# DBPIC18DIPv1_7.net
KiCad netlist of a schematic drawn in EAGLE
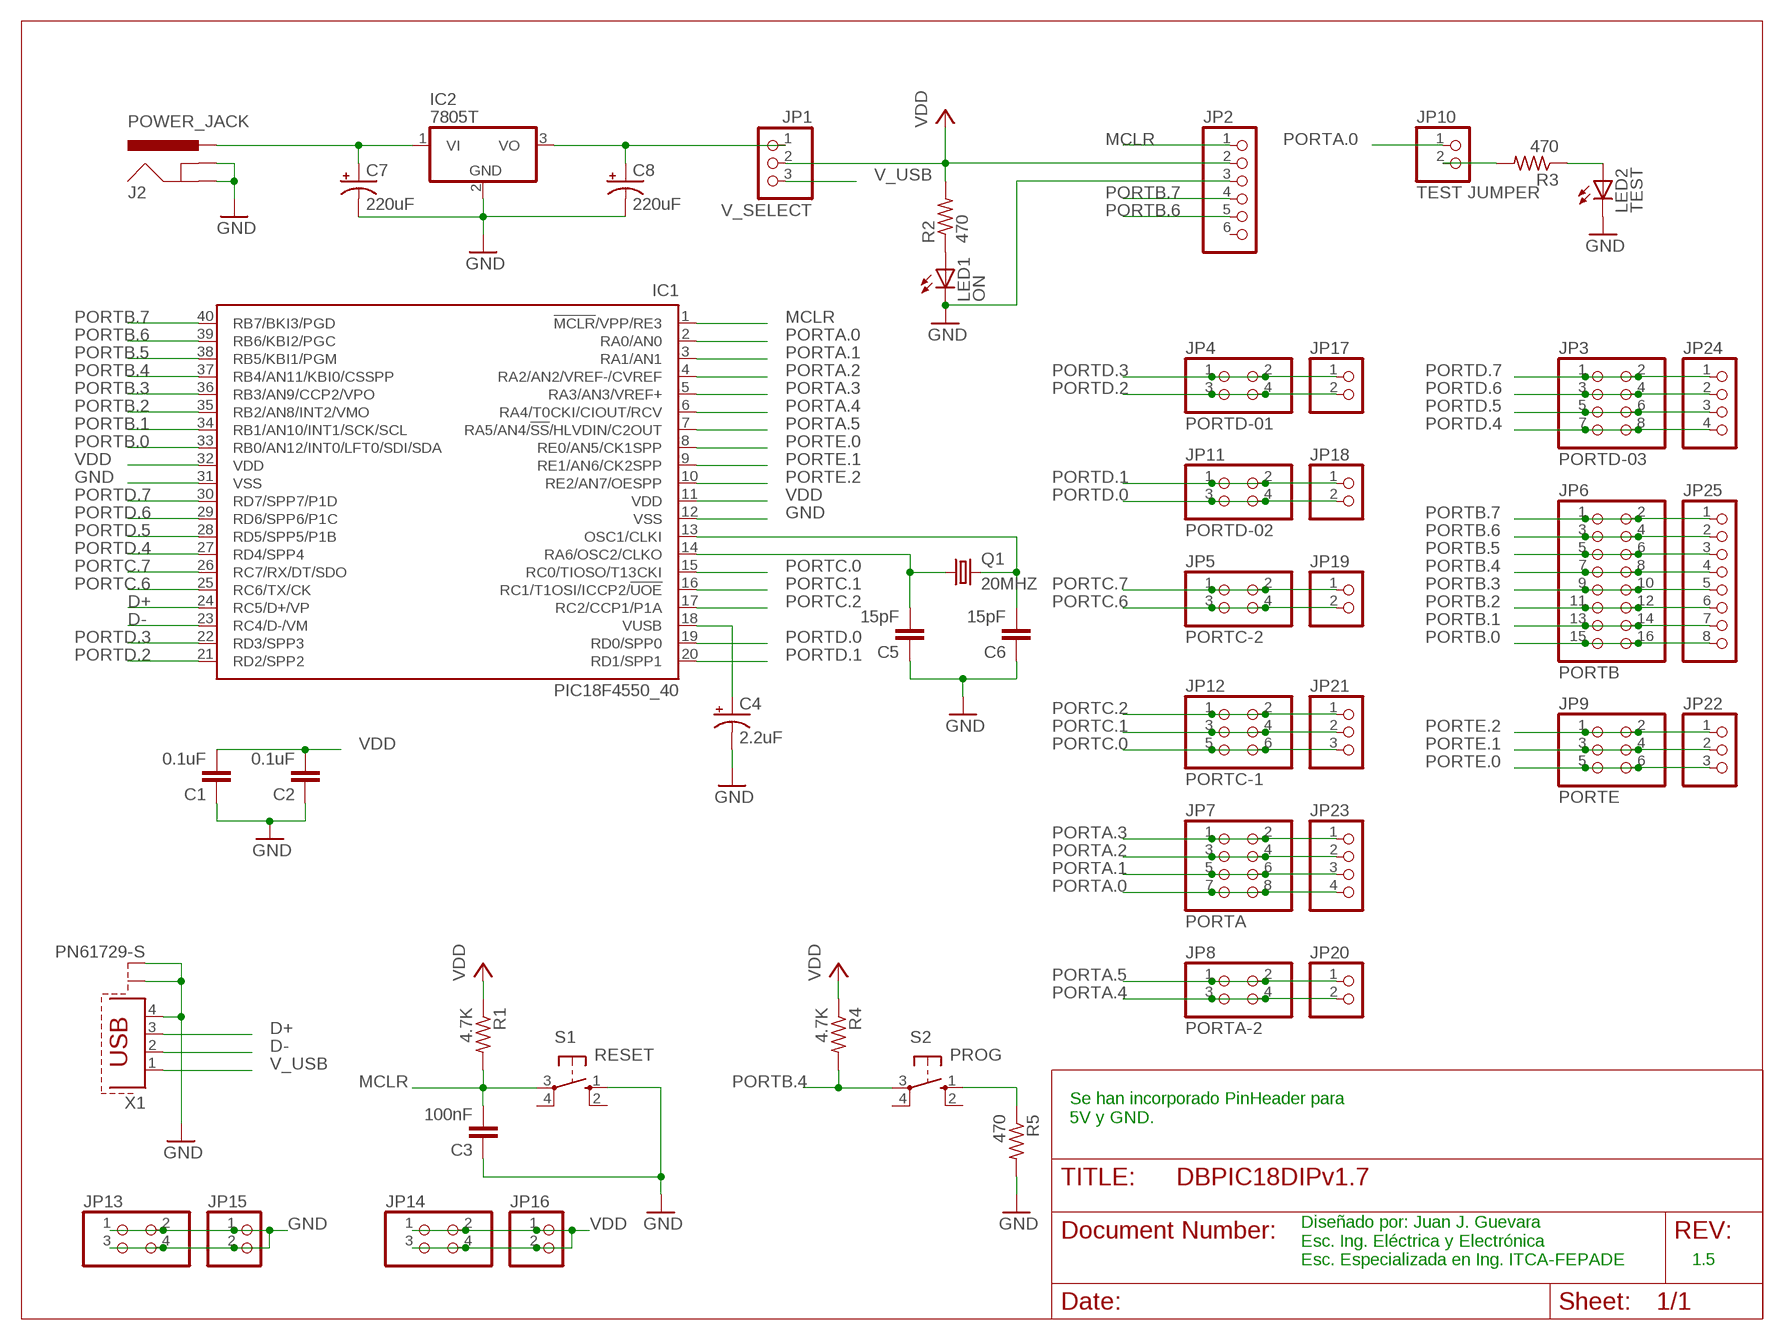
[diagram p0: schematic, sheet 1]

(export (version "E")
  (design (tool "Eeschema 10.0.6"))
  (components
    (comp (ref "C1")
      (value "0.1uF")
      (footprint "eagle-import:C2.5-2")
      (libsource (lib "eagle-import") (part "C2.5/2"))
    )
    (comp (ref "C2")
      (value "0.1uF")
      (footprint "eagle-import:C2.5-2")
      (libsource (lib "eagle-import") (part "C2.5/2"))
    )
    (comp (ref "C3")
      (value "100nF")
      (footprint "eagle-import:C2.5-2")
      (libsource (lib "eagle-import") (part "C2.5/2"))
    )
    (comp (ref "C4")
      (value "2.2uF")
      (footprint "eagle-import:E1,8-4")
      (libsource (lib "eagle-import") (part "CPOL-USE1.8-4"))
    )
    (comp (ref "C5")
      (value "15pF")
      (footprint "eagle-import:C2.5-2")
      (libsource (lib "eagle-import") (part "C2.5/2"))
    )
    (comp (ref "C6")
      (value "15pF")
      (footprint "eagle-import:C2.5-2")
      (libsource (lib "eagle-import") (part "C2.5/2"))
    )
    (comp (ref "C7")
      (value "220uF")
      (footprint "eagle-import:E2-5")
      (libsource (lib "eagle-import") (part "CPOL-USE2-5"))
    )
    (comp (ref "C8")
      (value "220uF")
      (footprint "eagle-import:E1,8-4")
      (libsource (lib "eagle-import") (part "CPOL-USE1.8-4"))
    )
    (comp (ref "IC1")
      (value "PIC18F4550_40")
      (footprint "eagle-import:DIL40")
      (fields (field (name "MF") "MICROCHIP") (field (name "MPN") "PIC18F4550-I/P"))
      (libsource (lib "eagle-import") (part "PIC18F4_40550"))
    )
    (comp (ref "IC2")
      (value "7805T")
      (footprint "eagle-import:TO220H")
      (libsource (lib "eagle-import") (part "78T05"))
    )
    (comp (ref "J2")
      (value "POWER_JACK")
      (footprint "eagle-import:POWER_JACK_PTH")
      (libsource (lib "eagle-import") (part "POWER_JACK"))
    )
    (comp (ref "JP1")
      (value "V_SELECT")
      (footprint "eagle-import:1X03")
      (libsource (lib "eagle-import") (part "PINHD-1X3"))
    )
    (comp (ref "JP2")
      (value "PINHD-1X6")
      (footprint "eagle-import:1X06")
      (libsource (lib "eagle-import") (part "PINHD-1X6"))
    )
    (comp (ref "JP3")
      (value "PORTD-03")
      (footprint "eagle-import:2X04")
      (libsource (lib "eagle-import") (part "PINHD-2X4"))
    )
    (comp (ref "JP4")
      (value "PORTD-01")
      (footprint "eagle-import:2X02")
      (libsource (lib "eagle-import") (part "PINHD-2X2"))
    )
    (comp (ref "JP5")
      (value "PORTC-2")
      (footprint "eagle-import:2X02")
      (libsource (lib "eagle-import") (part "PINHD-2X2"))
    )
    (comp (ref "JP6")
      (value "PORTB")
      (footprint "eagle-import:2X08")
      (libsource (lib "eagle-import") (part "PINHD-2X8"))
    )
    (comp (ref "JP7")
      (value "PORTA")
      (footprint "eagle-import:2X04")
      (libsource (lib "eagle-import") (part "PINHD-2X4"))
    )
    (comp (ref "JP8")
      (value "PORTA-2")
      (footprint "eagle-import:2X02")
      (libsource (lib "eagle-import") (part "PINHD-2X2"))
    )
    (comp (ref "JP9")
      (value "PORTE")
      (footprint "eagle-import:2X03")
      (libsource (lib "eagle-import") (part "PINHD-2X3"))
    )
    (comp (ref "JP10")
      (value "TEST JUMPER")
      (footprint "eagle-import:1X02")
      (libsource (lib "eagle-import") (part "PINHD-1X2"))
    )
    (comp (ref "JP11")
      (value "PORTD-02")
      (footprint "eagle-import:2X02")
      (libsource (lib "eagle-import") (part "PINHD-2X2"))
    )
    (comp (ref "JP12")
      (value "PORTC-1")
      (footprint "eagle-import:2X03")
      (libsource (lib "eagle-import") (part "PINHD-2X3"))
    )
    (comp (ref "JP13")
      (value "PINHD-2X2")
      (footprint "eagle-import:2X02")
      (libsource (lib "eagle-import") (part "PINHD-2X2"))
    )
    (comp (ref "JP14")
      (value "PINHD-2X2")
      (footprint "eagle-import:2X02")
      (libsource (lib "eagle-import") (part "PINHD-2X2"))
    )
    (comp (ref "JP15")
      (value "PINHD-1X2")
      (footprint "eagle-import:1X02")
      (libsource (lib "eagle-import") (part "PINHD-1X2"))
    )
    (comp (ref "JP16")
      (value "PINHD-1X2")
      (footprint "eagle-import:1X02")
      (libsource (lib "eagle-import") (part "PINHD-1X2"))
    )
    (comp (ref "JP17")
      (value "PINHD-1X2")
      (footprint "eagle-import:1X02")
      (libsource (lib "eagle-import") (part "PINHD-1X2"))
    )
    (comp (ref "JP18")
      (value "PINHD-1X2")
      (footprint "eagle-import:1X02")
      (libsource (lib "eagle-import") (part "PINHD-1X2"))
    )
    (comp (ref "JP19")
      (value "PINHD-1X2")
      (footprint "eagle-import:1X02")
      (libsource (lib "eagle-import") (part "PINHD-1X2"))
    )
    (comp (ref "JP20")
      (value "PINHD-1X2")
      (footprint "eagle-import:1X02")
      (libsource (lib "eagle-import") (part "PINHD-1X2"))
    )
    (comp (ref "JP21")
      (value "PINHD-1X3")
      (footprint "eagle-import:1X03")
      (libsource (lib "eagle-import") (part "PINHD-1X3"))
    )
    (comp (ref "JP22")
      (value "PINHD-1X3")
      (footprint "eagle-import:1X03")
      (libsource (lib "eagle-import") (part "PINHD-1X3"))
    )
    (comp (ref "JP23")
      (value "PINHD-1X4")
      (footprint "eagle-import:1X04")
      (libsource (lib "eagle-import") (part "PINHD-1X4"))
    )
    (comp (ref "JP24")
      (value "PINHD-1X4")
      (footprint "eagle-import:1X04")
      (libsource (lib "eagle-import") (part "PINHD-1X4"))
    )
    (comp (ref "JP25")
      (value "PINHD-1X8")
      (footprint "eagle-import:1X08")
      (libsource (lib "eagle-import") (part "PINHD-1X8"))
    )
    (comp (ref "LED1")
      (value "ON")
      (footprint "eagle-import:LED3MM")
      (libsource (lib "eagle-import") (part "LED3MM"))
    )
    (comp (ref "LED2")
      (value "TEST")
      (footprint "eagle-import:LED3MM")
      (libsource (lib "eagle-import") (part "LED3MM"))
    )
    (comp (ref "Q1")
      (value "20MHZ")
      (footprint "eagle-import:HC49_S")
      (libsource (lib "eagle-import") (part "CRYSTALHC49S"))
    )
    (comp (ref "R1")
      (value "4.7K")
      (footprint "eagle-import:0207_12")
      (libsource (lib "eagle-import") (part "R-US_0207/12"))
    )
    (comp (ref "R2")
      (value "470")
      (footprint "eagle-import:0207_12")
      (libsource (lib "eagle-import") (part "R-US_0207/12"))
    )
    (comp (ref "R3")
      (value "470")
      (footprint "eagle-import:0207_12")
      (libsource (lib "eagle-import") (part "R-US_0207/12"))
    )
    (comp (ref "R4")
      (value "4.7K")
      (footprint "eagle-import:0207_12")
      (libsource (lib "eagle-import") (part "R-US_0207/12"))
    )
    (comp (ref "R5")
      (value "470")
      (footprint "eagle-import:0207_12")
      (libsource (lib "eagle-import") (part "R-US_0207/12"))
    )
    (comp (ref "S1")
      (value "RESET")
      (footprint "eagle-import:B3F-10XX")
      (fields (field (name "MPN") "B3F-1000"))
      (libsource (lib "eagle-import") (part "10-XX"))
    )
    (comp (ref "S2")
      (value "PROG")
      (footprint "eagle-import:B3F-10XX")
      (fields (field (name "MPN") "B3F-1000"))
      (libsource (lib "eagle-import") (part "10-XX"))
    )
    (comp (ref "X1")
      (value "PN61729-S")
      (footprint "eagle-import:PN61729-S")
      (libsource (lib "eagle-import") (part "PN61729-S"))
    )
  )
  (nets
    (net (code "1") (name "/D+") (class "Default")
      (node (ref "IC1") (pin "24") (pinfunction "RC5/D+/VP_24") (pintype "bidirectional"))
      (node (ref "X1") (pin "3") (pinfunction "3_3") (pintype "passive"))
    )
    (net (code "2") (name "/D-") (class "Default")
      (node (ref "IC1") (pin "23") (pinfunction "RC4/D-/VM_23") (pintype "bidirectional"))
      (node (ref "X1") (pin "2") (pinfunction "2_2") (pintype "passive"))
    )
    (net (code "3") (name "/MCLR") (class "Default")
      (node (ref "C3") (pin "2") (pinfunction "2_2") (pintype "passive"))
      (node (ref "IC1") (pin "1") (pinfunction "~{MCLR}/VPP/RE3_1") (pintype "input"))
      (node (ref "JP2") (pin "1") (pinfunction "1_1") (pintype "passive"))
      (node (ref "R1") (pin "2") (pinfunction "2_2") (pintype "passive"))
      (node (ref "S1") (pin "3") (pinfunction "P_3") (pintype "passive"))
    )
    (net (code "4") (name "/PORTA.0") (class "Default")
      (node (ref "IC1") (pin "2") (pinfunction "RA0/AN0_2") (pintype "bidirectional"))
      (node (ref "JP10") (pin "1") (pinfunction "1_1") (pintype "passive"))
      (node (ref "JP23") (pin "4") (pinfunction "4_4") (pintype "passive"))
      (node (ref "JP7") (pin "7") (pinfunction "7_7") (pintype "passive"))
      (node (ref "JP7") (pin "8") (pinfunction "8_8") (pintype "passive"))
    )
    (net (code "5") (name "/PORTA.1") (class "Default")
      (node (ref "IC1") (pin "3") (pinfunction "RA1/AN1_3") (pintype "bidirectional"))
      (node (ref "JP23") (pin "3") (pinfunction "3_3") (pintype "passive"))
      (node (ref "JP7") (pin "5") (pinfunction "5_5") (pintype "passive"))
      (node (ref "JP7") (pin "6") (pinfunction "6_6") (pintype "passive"))
    )
    (net (code "6") (name "/PORTA.2") (class "Default")
      (node (ref "IC1") (pin "4") (pinfunction "RA2/AN2/VREF-/CVREF_4") (pintype "bidirectional"))
      (node (ref "JP23") (pin "2") (pinfunction "2_2") (pintype "passive"))
      (node (ref "JP7") (pin "3") (pinfunction "3_3") (pintype "passive"))
      (node (ref "JP7") (pin "4") (pinfunction "4_4") (pintype "passive"))
    )
    (net (code "7") (name "/PORTA.3") (class "Default")
      (node (ref "IC1") (pin "5") (pinfunction "RA3/AN3/VREF+_5") (pintype "bidirectional"))
      (node (ref "JP23") (pin "1") (pinfunction "1_1") (pintype "passive"))
      (node (ref "JP7") (pin "1") (pinfunction "1_1") (pintype "passive"))
      (node (ref "JP7") (pin "2") (pinfunction "2_2") (pintype "passive"))
    )
    (net (code "8") (name "/PORTA.4") (class "Default")
      (node (ref "IC1") (pin "6") (pinfunction "RA4/T0CKI/CIOUT/RCV_6") (pintype "bidirectional"))
      (node (ref "JP20") (pin "2") (pinfunction "2_2") (pintype "passive"))
      (node (ref "JP8") (pin "3") (pinfunction "3_3") (pintype "passive"))
      (node (ref "JP8") (pin "4") (pinfunction "4_4") (pintype "passive"))
    )
    (net (code "9") (name "/PORTA.5") (class "Default")
      (node (ref "IC1") (pin "7") (pinfunction "RA5/AN4/~{SS}/HLVDIN/C2OUT_7") (pintype "bidirectional"))
      (node (ref "JP20") (pin "1") (pinfunction "1_1") (pintype "passive"))
      (node (ref "JP8") (pin "1") (pinfunction "1_1") (pintype "passive"))
      (node (ref "JP8") (pin "2") (pinfunction "2_2") (pintype "passive"))
    )
    (net (code "10") (name "/PORTB.0") (class "Default")
      (node (ref "IC1") (pin "33") (pinfunction "RB0/AN12/INT0/LFT0/SDI/SDA_33") (pintype "bidirectional"))
      (node (ref "JP25") (pin "8") (pinfunction "8_8") (pintype "passive"))
      (node (ref "JP6") (pin "15") (pinfunction "15_15") (pintype "passive"))
      (node (ref "JP6") (pin "16") (pinfunction "16_16") (pintype "passive"))
    )
    (net (code "11") (name "/PORTB.1") (class "Default")
      (node (ref "IC1") (pin "34") (pinfunction "RB1/AN10/INT1/SCK/SCL_34") (pintype "bidirectional"))
      (node (ref "JP25") (pin "7") (pinfunction "7_7") (pintype "passive"))
      (node (ref "JP6") (pin "13") (pinfunction "13_13") (pintype "passive"))
      (node (ref "JP6") (pin "14") (pinfunction "14_14") (pintype "passive"))
    )
    (net (code "12") (name "/PORTB.2") (class "Default")
      (node (ref "IC1") (pin "35") (pinfunction "RB2/AN8/INT2/VMO_35") (pintype "bidirectional"))
      (node (ref "JP25") (pin "6") (pinfunction "6_6") (pintype "passive"))
      (node (ref "JP6") (pin "11") (pinfunction "11_11") (pintype "passive"))
      (node (ref "JP6") (pin "12") (pinfunction "12_12") (pintype "passive"))
    )
    (net (code "13") (name "/PORTB.3") (class "Default")
      (node (ref "IC1") (pin "36") (pinfunction "RB3/AN9/CCP2/VPO_36") (pintype "bidirectional"))
      (node (ref "JP25") (pin "5") (pinfunction "5_5") (pintype "passive"))
      (node (ref "JP6") (pin "10") (pinfunction "10_10") (pintype "passive"))
      (node (ref "JP6") (pin "9") (pinfunction "9_9") (pintype "passive"))
    )
    (net (code "14") (name "/PORTB.4") (class "Default")
      (node (ref "IC1") (pin "37") (pinfunction "RB4/AN11/KBI0/CSSPP_37") (pintype "bidirectional"))
      (node (ref "JP25") (pin "4") (pinfunction "4_4") (pintype "passive"))
      (node (ref "JP6") (pin "7") (pinfunction "7_7") (pintype "passive"))
      (node (ref "JP6") (pin "8") (pinfunction "8_8") (pintype "passive"))
      (node (ref "R4") (pin "2") (pinfunction "2_2") (pintype "passive"))
      (node (ref "S2") (pin "3") (pinfunction "P_3") (pintype "passive"))
    )
    (net (code "15") (name "/PORTB.5") (class "Default")
      (node (ref "IC1") (pin "38") (pinfunction "RB5/KBI1/PGM_38") (pintype "bidirectional"))
      (node (ref "JP25") (pin "3") (pinfunction "3_3") (pintype "passive"))
      (node (ref "JP6") (pin "5") (pinfunction "5_5") (pintype "passive"))
      (node (ref "JP6") (pin "6") (pinfunction "6_6") (pintype "passive"))
    )
    (net (code "16") (name "/PORTB.6") (class "Default")
      (node (ref "IC1") (pin "39") (pinfunction "RB6/KBI2/PGC_39") (pintype "bidirectional"))
      (node (ref "JP2") (pin "5") (pinfunction "5_5") (pintype "passive"))
      (node (ref "JP25") (pin "2") (pinfunction "2_2") (pintype "passive"))
      (node (ref "JP6") (pin "3") (pinfunction "3_3") (pintype "passive"))
      (node (ref "JP6") (pin "4") (pinfunction "4_4") (pintype "passive"))
    )
    (net (code "17") (name "/PORTB.7") (class "Default")
      (node (ref "IC1") (pin "40") (pinfunction "RB7/BKI3/PGD_40") (pintype "bidirectional"))
      (node (ref "JP2") (pin "4") (pinfunction "4_4") (pintype "passive"))
      (node (ref "JP25") (pin "1") (pinfunction "1_1") (pintype "passive"))
      (node (ref "JP6") (pin "1") (pinfunction "1_1") (pintype "passive"))
      (node (ref "JP6") (pin "2") (pinfunction "2_2") (pintype "passive"))
    )
    (net (code "18") (name "/PORTC.0") (class "Default")
      (node (ref "IC1") (pin "15") (pinfunction "RC0/TIOSO/T13CKI_15") (pintype "bidirectional"))
      (node (ref "JP12") (pin "5") (pinfunction "5_5") (pintype "passive"))
      (node (ref "JP12") (pin "6") (pinfunction "6_6") (pintype "passive"))
      (node (ref "JP21") (pin "3") (pinfunction "3_3") (pintype "passive"))
    )
    (net (code "19") (name "/PORTC.1") (class "Default")
      (node (ref "IC1") (pin "16") (pinfunction "RC1/T1OSI/ICCP2/~{UOE}_16") (pintype "bidirectional"))
      (node (ref "JP12") (pin "3") (pinfunction "3_3") (pintype "passive"))
      (node (ref "JP12") (pin "4") (pinfunction "4_4") (pintype "passive"))
      (node (ref "JP21") (pin "2") (pinfunction "2_2") (pintype "passive"))
    )
    (net (code "20") (name "/PORTC.2") (class "Default")
      (node (ref "IC1") (pin "17") (pinfunction "RC2/CCP1/P1A_17") (pintype "bidirectional"))
      (node (ref "JP12") (pin "1") (pinfunction "1_1") (pintype "passive"))
      (node (ref "JP12") (pin "2") (pinfunction "2_2") (pintype "passive"))
      (node (ref "JP21") (pin "1") (pinfunction "1_1") (pintype "passive"))
    )
    (net (code "21") (name "/PORTC.6") (class "Default")
      (node (ref "IC1") (pin "25") (pinfunction "RC6/TX/CK_25") (pintype "bidirectional"))
      (node (ref "JP19") (pin "2") (pinfunction "2_2") (pintype "passive"))
      (node (ref "JP5") (pin "3") (pinfunction "3_3") (pintype "passive"))
      (node (ref "JP5") (pin "4") (pinfunction "4_4") (pintype "passive"))
    )
    (net (code "22") (name "/PORTC.7") (class "Default")
      (node (ref "IC1") (pin "26") (pinfunction "RC7/RX/DT/SDO_26") (pintype "bidirectional"))
      (node (ref "JP19") (pin "1") (pinfunction "1_1") (pintype "passive"))
      (node (ref "JP5") (pin "1") (pinfunction "1_1") (pintype "passive"))
      (node (ref "JP5") (pin "2") (pinfunction "2_2") (pintype "passive"))
    )
    (net (code "23") (name "/PORTD.0") (class "Default")
      (node (ref "IC1") (pin "19") (pinfunction "RD0/SPP0_19") (pintype "bidirectional"))
      (node (ref "JP11") (pin "3") (pinfunction "3_3") (pintype "passive"))
      (node (ref "JP11") (pin "4") (pinfunction "4_4") (pintype "passive"))
      (node (ref "JP18") (pin "2") (pinfunction "2_2") (pintype "passive"))
    )
    (net (code "24") (name "/PORTD.1") (class "Default")
      (node (ref "IC1") (pin "20") (pinfunction "RD1/SPP1_20") (pintype "bidirectional"))
      (node (ref "JP11") (pin "1") (pinfunction "1_1") (pintype "passive"))
      (node (ref "JP11") (pin "2") (pinfunction "2_2") (pintype "passive"))
      (node (ref "JP18") (pin "1") (pinfunction "1_1") (pintype "passive"))
    )
    (net (code "25") (name "/PORTD.2") (class "Default")
      (node (ref "IC1") (pin "21") (pinfunction "RD2/SPP2_21") (pintype "bidirectional"))
      (node (ref "JP17") (pin "2") (pinfunction "2_2") (pintype "passive"))
      (node (ref "JP4") (pin "3") (pinfunction "3_3") (pintype "passive"))
      (node (ref "JP4") (pin "4") (pinfunction "4_4") (pintype "passive"))
    )
    (net (code "26") (name "/PORTD.3") (class "Default")
      (node (ref "IC1") (pin "22") (pinfunction "RD3/SPP3_22") (pintype "bidirectional"))
      (node (ref "JP17") (pin "1") (pinfunction "1_1") (pintype "passive"))
      (node (ref "JP4") (pin "1") (pinfunction "1_1") (pintype "passive"))
      (node (ref "JP4") (pin "2") (pinfunction "2_2") (pintype "passive"))
    )
    (net (code "27") (name "/PORTD.4") (class "Default")
      (node (ref "IC1") (pin "27") (pinfunction "RD4/SPP4_27") (pintype "bidirectional"))
      (node (ref "JP24") (pin "4") (pinfunction "4_4") (pintype "passive"))
      (node (ref "JP3") (pin "7") (pinfunction "7_7") (pintype "passive"))
      (node (ref "JP3") (pin "8") (pinfunction "8_8") (pintype "passive"))
    )
    (net (code "28") (name "/PORTD.5") (class "Default")
      (node (ref "IC1") (pin "28") (pinfunction "RD5/SPP5/P1B_28") (pintype "bidirectional"))
      (node (ref "JP24") (pin "3") (pinfunction "3_3") (pintype "passive"))
      (node (ref "JP3") (pin "5") (pinfunction "5_5") (pintype "passive"))
      (node (ref "JP3") (pin "6") (pinfunction "6_6") (pintype "passive"))
    )
    (net (code "29") (name "/PORTD.6") (class "Default")
      (node (ref "IC1") (pin "29") (pinfunction "RD6/SPP6/P1C_29") (pintype "bidirectional"))
      (node (ref "JP24") (pin "2") (pinfunction "2_2") (pintype "passive"))
      (node (ref "JP3") (pin "3") (pinfunction "3_3") (pintype "passive"))
      (node (ref "JP3") (pin "4") (pinfunction "4_4") (pintype "passive"))
    )
    (net (code "30") (name "/PORTD.7") (class "Default")
      (node (ref "IC1") (pin "30") (pinfunction "RD7/SPP7/P1D_30") (pintype "bidirectional"))
      (node (ref "JP24") (pin "1") (pinfunction "1_1") (pintype "passive"))
      (node (ref "JP3") (pin "1") (pinfunction "1_1") (pintype "passive"))
      (node (ref "JP3") (pin "2") (pinfunction "2_2") (pintype "passive"))
    )
    (net (code "31") (name "/PORTE.0") (class "Default")
      (node (ref "IC1") (pin "8") (pinfunction "RE0/AN5/CK1SPP_8") (pintype "bidirectional"))
      (node (ref "JP22") (pin "3") (pinfunction "3_3") (pintype "passive"))
      (node (ref "JP9") (pin "5") (pinfunction "5_5") (pintype "passive"))
      (node (ref "JP9") (pin "6") (pinfunction "6_6") (pintype "passive"))
    )
    (net (code "32") (name "/PORTE.1") (class "Default")
      (node (ref "IC1") (pin "9") (pinfunction "RE1/AN6/CK2SPP_9") (pintype "bidirectional"))
      (node (ref "JP22") (pin "2") (pinfunction "2_2") (pintype "passive"))
      (node (ref "JP9") (pin "3") (pinfunction "3_3") (pintype "passive"))
      (node (ref "JP9") (pin "4") (pinfunction "4_4") (pintype "passive"))
    )
    (net (code "33") (name "/PORTE.2") (class "Default")
      (node (ref "IC1") (pin "10") (pinfunction "RE2/AN7/OESPP_10") (pintype "bidirectional"))
      (node (ref "JP22") (pin "1") (pinfunction "1_1") (pintype "passive"))
      (node (ref "JP9") (pin "1") (pinfunction "1_1") (pintype "passive"))
      (node (ref "JP9") (pin "2") (pinfunction "2_2") (pintype "passive"))
    )
    (net (code "34") (name "/V_USB") (class "Default")
      (node (ref "JP1") (pin "3") (pinfunction "3_3") (pintype "passive"))
      (node (ref "X1") (pin "1") (pinfunction "1_1") (pintype "passive"))
    )
    (net (code "35") (name "GND") (class "Default")
      (node (ref "C1") (pin "1") (pinfunction "1_1") (pintype "passive"))
      (node (ref "C2") (pin "1") (pinfunction "1_1") (pintype "passive"))
      (node (ref "C3") (pin "1") (pinfunction "1_1") (pintype "passive"))
      (node (ref "C4") (pin "-") (pinfunction "-_-") (pintype "passive"))
      (node (ref "C5") (pin "1") (pinfunction "1_1") (pintype "passive"))
      (node (ref "C6") (pin "1") (pinfunction "1_1") (pintype "passive"))
      (node (ref "C7") (pin "-") (pinfunction "-_-") (pintype "passive"))
      (node (ref "C8") (pin "-") (pinfunction "-_-") (pintype "passive"))
      (node (ref "IC1") (pin "12") (pinfunction "VSS_12") (pintype "power_in"))
      (node (ref "IC1") (pin "31") (pinfunction "VSS_31") (pintype "power_in"))
      (node (ref "IC2") (pin "2") (pinfunction "GND_2") (pintype "passive"))
      (node (ref "J2") (pin "GND") (pinfunction "GND_GND") (pintype "bidirectional"))
      (node (ref "J2") (pin "GNDBREAK") (pinfunction "GNDBREAK_GNDBREAK") (pintype "bidirectional"))
      (node (ref "JP13") (pin "1") (pinfunction "1_1") (pintype "passive"))
      (node (ref "JP13") (pin "2") (pinfunction "2_2") (pintype "passive"))
      (node (ref "JP13") (pin "3") (pinfunction "3_3") (pintype "passive"))
      (node (ref "JP13") (pin "4") (pinfunction "4_4") (pintype "passive"))
      (node (ref "JP15") (pin "1") (pinfunction "1_1") (pintype "passive"))
      (node (ref "JP15") (pin "2") (pinfunction "2_2") (pintype "passive"))
      (node (ref "JP2") (pin "3") (pinfunction "3_3") (pintype "passive"))
      (node (ref "LED1") (pin "K") (pinfunction "C_K") (pintype "passive"))
      (node (ref "LED2") (pin "K") (pinfunction "C_K") (pintype "passive"))
      (node (ref "R5") (pin "2") (pinfunction "2_2") (pintype "passive"))
      (node (ref "S1") (pin "1") (pinfunction "S_1") (pintype "passive"))
      (node (ref "X1") (pin "4") (pinfunction "4_4") (pintype "passive"))
      (node (ref "X1") (pin "S1") (pinfunction "S1_S1") (pintype "passive"))
      (node (ref "X1") (pin "S2") (pinfunction "S2_S2") (pintype "passive"))
    )
    (net (code "36") (name "Net-(IC1-OSC1{slash}CLKI)") (class "Default")
      (node (ref "C6") (pin "2") (pinfunction "2_2") (pintype "passive"))
      (node (ref "IC1") (pin "13") (pinfunction "OSC1/CLKI_13") (pintype "input"))
      (node (ref "Q1") (pin "2") (pinfunction "2_2") (pintype "passive"))
    )
    (net (code "37") (name "Net-(IC1-RA6{slash}OSC2{slash}CLKO)") (class "Default")
      (node (ref "C5") (pin "2") (pinfunction "2_2") (pintype "passive"))
      (node (ref "IC1") (pin "14") (pinfunction "RA6/OSC2/CLKO_14") (pintype "output"))
      (node (ref "Q1") (pin "1") (pinfunction "1_1") (pintype "passive"))
    )
    (net (code "38") (name "Net-(IC1-VUSB)") (class "Default")
      (node (ref "C4") (pin "+") (pinfunction "+_+") (pintype "passive"))
      (node (ref "IC1") (pin "18") (pinfunction "VUSB_18") (pintype "bidirectional"))
    )
    (net (code "39") (name "Net-(IC2-VI)") (class "Default")
      (node (ref "C7") (pin "+") (pinfunction "+_+") (pintype "passive"))
      (node (ref "IC2") (pin "1") (pinfunction "VI_1") (pintype "input"))
      (node (ref "J2") (pin "PWR") (pinfunction "PWR_PWR") (pintype "bidirectional"))
    )
    (net (code "40") (name "Net-(IC2-VO)") (class "Default")
      (node (ref "C8") (pin "+") (pinfunction "+_+") (pintype "passive"))
      (node (ref "IC2") (pin "3") (pinfunction "VO_3") (pintype "passive"))
      (node (ref "JP1") (pin "1") (pinfunction "1_1") (pintype "passive"))
    )
    (net (code "41") (name "Net-(JP10-Pad2)") (class "Default")
      (node (ref "JP10") (pin "2") (pinfunction "2_2") (pintype "passive"))
      (node (ref "R3") (pin "2") (pinfunction "2_2") (pintype "passive"))
    )
    (net (code "42") (name "Net-(LED1-PadA)") (class "Default")
      (node (ref "LED1") (pin "A") (pinfunction "A_A") (pintype "passive"))
      (node (ref "R2") (pin "1") (pinfunction "1_1") (pintype "passive"))
    )
    (net (code "43") (name "Net-(LED2-PadA)") (class "Default")
      (node (ref "LED2") (pin "A") (pinfunction "A_A") (pintype "passive"))
      (node (ref "R3") (pin "1") (pinfunction "1_1") (pintype "passive"))
    )
    (net (code "44") (name "Net-(S2-S)") (class "Default")
      (node (ref "R5") (pin "1") (pinfunction "1_1") (pintype "passive"))
      (node (ref "S2") (pin "1") (pinfunction "S_1") (pintype "passive"))
    )
    (net (code "45") (name "VDD") (class "Default")
      (node (ref "C1") (pin "2") (pinfunction "2_2") (pintype "passive"))
      (node (ref "C2") (pin "2") (pinfunction "2_2") (pintype "passive"))
      (node (ref "IC1") (pin "11") (pinfunction "VDD_11") (pintype "power_in"))
      (node (ref "IC1") (pin "32") (pinfunction "VDD_32") (pintype "power_in"))
      (node (ref "JP1") (pin "2") (pinfunction "2_2") (pintype "passive"))
      (node (ref "JP14") (pin "1") (pinfunction "1_1") (pintype "passive"))
      (node (ref "JP14") (pin "2") (pinfunction "2_2") (pintype "passive"))
      (node (ref "JP14") (pin "3") (pinfunction "3_3") (pintype "passive"))
      (node (ref "JP14") (pin "4") (pinfunction "4_4") (pintype "passive"))
      (node (ref "JP16") (pin "1") (pinfunction "1_1") (pintype "passive"))
      (node (ref "JP16") (pin "2") (pinfunction "2_2") (pintype "passive"))
      (node (ref "JP2") (pin "2") (pinfunction "2_2") (pintype "passive"))
      (node (ref "R1") (pin "1") (pinfunction "1_1") (pintype "passive"))
      (node (ref "R2") (pin "2") (pinfunction "2_2") (pintype "passive"))
      (node (ref "R4") (pin "1") (pinfunction "1_1") (pintype "passive"))
    )
    (net (code "46") (name "unconnected-(JP2-Pad6)") (class "Default")
      (node (ref "JP2") (pin "6") (pinfunction "6_6") (pintype "passive"))
    )
    (net (code "47") (name "unconnected-(S1-P1-Pad4)") (class "Default")
      (node (ref "S1") (pin "4") (pinfunction "P1_4") (pintype "passive"))
    )
    (net (code "48") (name "unconnected-(S1-S1-Pad2)") (class "Default")
      (node (ref "S1") (pin "2") (pinfunction "S1_2") (pintype "passive"))
    )
    (net (code "49") (name "unconnected-(S2-P1-Pad4)") (class "Default")
      (node (ref "S2") (pin "4") (pinfunction "P1_4") (pintype "passive"))
    )
    (net (code "50") (name "unconnected-(S2-S1-Pad2)") (class "Default")
      (node (ref "S2") (pin "2") (pinfunction "S1_2") (pintype "passive"))
    )
  )
)
